# MotorDriver.net
KiCad netlist of a schematic drawn in Altium Designer
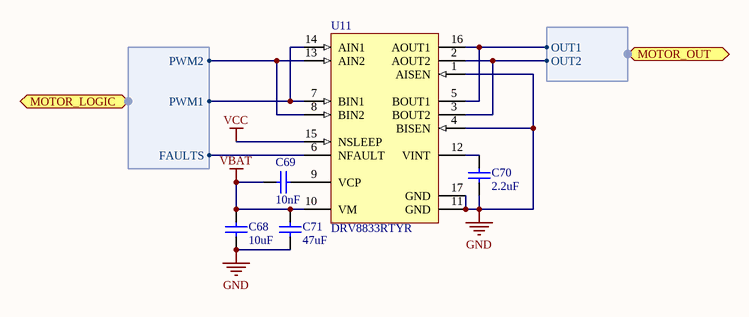
[diagram p0: MotorDriver.SchDoc]

(export (version "E")
  (design (tool "Eeschema 10.0.6"))
  (components
    (comp (ref "C68")
      (value "10uF")
      (footprint "C0603[1608X92]")
      (description "10uF 16V 10% 0603 (1608 Metric)")
      (fields (field (name "PARTNUMBER") "GRM188R61C106KAALD") (field (name "MANUFACTURER") "Murata"))
      (libsource (lib "Capacitors") (part "CAP_10uF_16V_0603_10%"))
    )
    (comp (ref "C69")
      (value "10nF")
      (footprint "C0402[1005X55]")
      (description "10nF 50V 10% 0402 (1005 Metric)")
      (fields (field (name "PARTNUMBER") "GCM155R71H103KA55D") (field (name "MANUFACTURER") "Murata"))
      (libsource (lib "Capacitors") (part "CAP_10nF_50V_0402_10%"))
    )
    (comp (ref "C70")
      (value "2.2uF")
      (footprint "C0402[1005X55]")
      (description "2.2uF 6.3V 20% 0402 (1005 Metric)")
      (fields (field (name "PARTNUMBER") "GRM155R60J225ME15D") (field (name "MANUFACTURER") "Murata"))
      (libsource (lib "Capacitors") (part "CAP_2.2uF_6.3V_0402_20%"))
    )
    (comp (ref "C71")
      (value "47uF")
      (footprint "C1206[3216X160]")
      (description "47uF 6.3V 10% 1206 (3216 Metric)")
      (fields (field (name "PARTNUMBER") "GRM31CR60J476KE19L") (field (name "MANUFACTURER") "Murata"))
      (libsource (lib "Capacitors") (part "CAP_47uF_6.3V_1206_10%"))
    )
    (comp (ref "U11")
      (value "DRV8833RTYR")
      (footprint "QFN-16 (0.65mm)")
      (fields (field (name "MANUFACTURER") "Texas Instruments"))
      (libsource (lib "ICs") (part "DRV8833RTYR"))
    )
  )
  (nets
    (net (code "3") (name "/FAULTS") (class "Default")
      (node (ref "U11") (pin "6") (pinfunction "NFAULT_6") (pintype "open_collector"))
    )
    (net (code "4") (name "/OUT1") (class "Default")
      (node (ref "U11") (pin "16") (pinfunction "AOUT1_16") (pintype "tri_state"))
      (node (ref "U11") (pin "5") (pinfunction "BOUT1_5") (pintype "tri_state"))
    )
    (net (code "5") (name "/OUT2") (class "Default")
      (node (ref "U11") (pin "2") (pinfunction "AOUT2_2") (pintype "tri_state"))
      (node (ref "U11") (pin "3") (pinfunction "BOUT2_3") (pintype "tri_state"))
    )
    (net (code "6") (name "/PWM1") (class "Default")
      (node (ref "U11") (pin "14") (pinfunction "AIN1_14") (pintype "input"))
      (node (ref "U11") (pin "7") (pinfunction "BIN1_7") (pintype "input"))
    )
    (net (code "7") (name "/PWM2") (class "Default")
      (node (ref "U11") (pin "13") (pinfunction "AIN2_13") (pintype "input"))
      (node (ref "U11") (pin "8") (pinfunction "BIN2_8") (pintype "input"))
    )
    (net (code "10") (name "GND") (class "Default")
      (node (ref "C68") (pin "1") (pinfunction "1_1") (pintype "passive"))
      (node (ref "C70") (pin "1") (pinfunction "1_1") (pintype "passive"))
      (node (ref "C71") (pin "2") (pinfunction "2_2") (pintype "passive"))
      (node (ref "U11") (pin "1") (pinfunction "AISEN_1") (pintype "input"))
      (node (ref "U11") (pin "11") (pinfunction "GND_11") (pintype "power_in"))
      (node (ref "U11") (pin "17") (pinfunction "GND_17") (pintype "power_in"))
      (node (ref "U11") (pin "4") (pinfunction "BISEN_4") (pintype "input"))
    )
    (net (code "11") (name "Net-(U11-VCP)") (class "Default")
      (node (ref "C69") (pin "2") (pinfunction "2_2") (pintype "passive"))
      (node (ref "U11") (pin "9") (pinfunction "VCP_9") (pintype "passive"))
    )
    (net (code "12") (name "Net-(U11-VINT)") (class "Default")
      (node (ref "C70") (pin "2") (pinfunction "2_2") (pintype "passive"))
      (node (ref "U11") (pin "12") (pinfunction "VINT_12") (pintype "passive"))
    )
    (net (code "13") (name "VBAT") (class "Default")
      (node (ref "C68") (pin "2") (pinfunction "2_2") (pintype "passive"))
      (node (ref "C69") (pin "1") (pinfunction "1_1") (pintype "passive"))
      (node (ref "C71") (pin "1") (pinfunction "1_1") (pintype "passive"))
      (node (ref "U11") (pin "10") (pinfunction "VM_10") (pintype "power_in"))
    )
    (net (code "14") (name "VCC") (class "Default")
      (node (ref "U11") (pin "15") (pinfunction "NSLEEP_15") (pintype "input"))
    )
  )
)
